# Low_Pass_Filter.net
KiCad netlist of a schematic drawn in Altium Designer
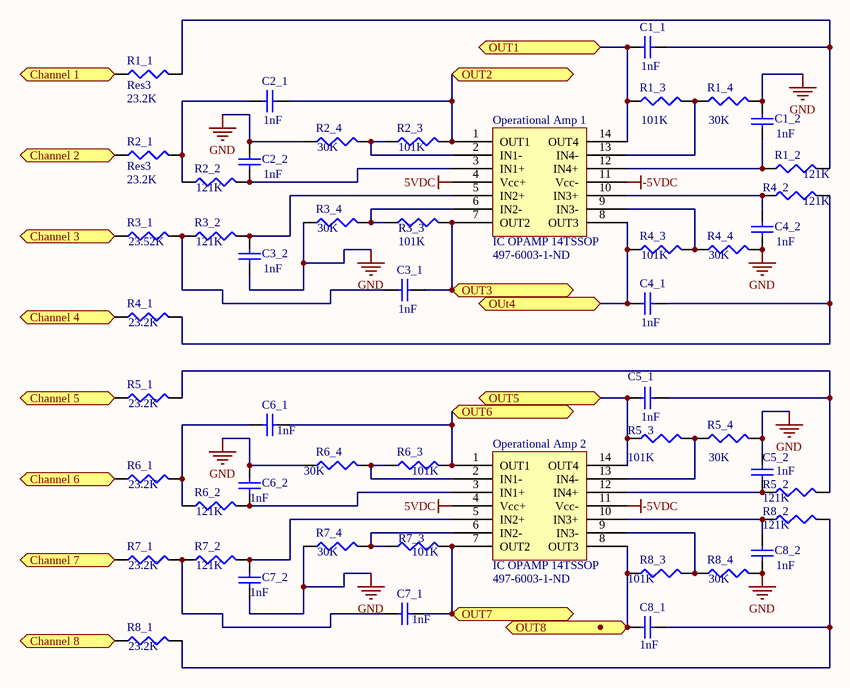
[diagram p0: Low Pass Filter.SchDoc]

(export (version "E")
  (design (tool "Eeschema 10.0.6"))
  (components
    (comp (ref "C1_1")
      (value "1nF")
      (footprint "6-0805_N")
      (description "Capacitor (Semiconductor SIM Model)")
      (fields (field (name "Comment") "Cap Semi") (field (name "PUBLISHER") "Altium Limited"))
      (libsource (lib "Miscellaneous Devices") (part "Cap Semi"))
    )
    (comp (ref "C1_2")
      (value "1nF")
      (footprint "6-0805_N")
      (description "Capacitor (Semiconductor SIM Model)")
      (fields (field (name "Comment") "Cap Semi") (field (name "PUBLISHER") "Altium Limited"))
      (libsource (lib "Miscellaneous Devices") (part "Cap Semi"))
    )
    (comp (ref "C2_1")
      (value "1nF")
      (footprint "6-0805_N")
      (description "Capacitor (Semiconductor SIM Model)")
      (fields (field (name "Comment") "Cap Semi") (field (name "PUBLISHER") "Altium Limited"))
      (libsource (lib "Miscellaneous Devices") (part "Cap Semi"))
    )
    (comp (ref "C2_2")
      (value "1nF")
      (footprint "6-0805_N")
      (description "Capacitor (Semiconductor SIM Model)")
      (fields (field (name "Comment") "Cap Semi") (field (name "PUBLISHER") "Altium Limited"))
      (libsource (lib "Miscellaneous Devices") (part "Cap Semi"))
    )
    (comp (ref "C3_1")
      (value "1nF")
      (footprint "6-0805_N")
      (description "Capacitor (Semiconductor SIM Model)")
      (fields (field (name "Comment") "Cap Semi") (field (name "PUBLISHER") "Altium Limited"))
      (libsource (lib "Miscellaneous Devices") (part "Cap Semi"))
    )
    (comp (ref "C3_2")
      (value "1nF")
      (footprint "6-0805_N")
      (description "Capacitor (Semiconductor SIM Model)")
      (fields (field (name "Comment") "Cap Semi") (field (name "PUBLISHER") "Altium Limited"))
      (libsource (lib "Miscellaneous Devices") (part "Cap Semi"))
    )
    (comp (ref "C4_1")
      (value "1nF")
      (footprint "6-0805_N")
      (description "Capacitor (Semiconductor SIM Model)")
      (fields (field (name "Comment") "Cap Semi") (field (name "PUBLISHER") "Altium Limited"))
      (libsource (lib "Miscellaneous Devices") (part "Cap Semi"))
    )
    (comp (ref "C4_2")
      (value "1nF")
      (footprint "6-0805_N")
      (description "Capacitor (Semiconductor SIM Model)")
      (fields (field (name "Comment") "Cap Semi") (field (name "PUBLISHER") "Altium Limited"))
      (libsource (lib "Miscellaneous Devices") (part "Cap Semi"))
    )
    (comp (ref "C5_1")
      (value "1nF")
      (footprint "6-0805_N")
      (description "Capacitor (Semiconductor SIM Model)")
      (fields (field (name "Comment") "Cap Semi") (field (name "PUBLISHER") "Altium Limited"))
      (libsource (lib "Miscellaneous Devices") (part "Cap Semi"))
    )
    (comp (ref "C5_2")
      (value "1nF")
      (footprint "6-0805_N")
      (description "Capacitor (Semiconductor SIM Model)")
      (fields (field (name "Comment") "Cap Semi") (field (name "PUBLISHER") "Altium Limited"))
      (libsource (lib "Miscellaneous Devices") (part "Cap Semi"))
    )
    (comp (ref "C6_1")
      (value "1nF")
      (footprint "6-0805_N")
      (description "Capacitor (Semiconductor SIM Model)")
      (fields (field (name "Comment") "Cap Semi") (field (name "PUBLISHER") "Altium Limited"))
      (libsource (lib "Miscellaneous Devices") (part "Cap Semi"))
    )
    (comp (ref "C6_2")
      (value "1nF")
      (footprint "6-0805_N")
      (description "Capacitor (Semiconductor SIM Model)")
      (fields (field (name "Comment") "Cap Semi") (field (name "PUBLISHER") "Altium Limited"))
      (libsource (lib "Miscellaneous Devices") (part "Cap Semi"))
    )
    (comp (ref "C7_1")
      (value "1nF")
      (footprint "6-0805_N")
      (description "Capacitor (Semiconductor SIM Model)")
      (fields (field (name "Comment") "Cap Semi") (field (name "PUBLISHER") "Altium Limited"))
      (libsource (lib "Miscellaneous Devices") (part "Cap Semi"))
    )
    (comp (ref "C7_2")
      (value "1nF")
      (footprint "6-0805_N")
      (description "Capacitor (Semiconductor SIM Model)")
      (fields (field (name "Comment") "Cap Semi") (field (name "PUBLISHER") "Altium Limited"))
      (libsource (lib "Miscellaneous Devices") (part "Cap Semi"))
    )
    (comp (ref "C8_1")
      (value "1nF")
      (footprint "6-0805_N")
      (description "Capacitor (Semiconductor SIM Model)")
      (fields (field (name "Comment") "Cap Semi") (field (name "PUBLISHER") "Altium Limited"))
      (libsource (lib "Miscellaneous Devices") (part "Cap Semi"))
    )
    (comp (ref "C8_2")
      (value "1nF")
      (footprint "6-0805_N")
      (description "Capacitor (Semiconductor SIM Model)")
      (fields (field (name "Comment") "Cap Semi") (field (name "PUBLISHER") "Altium Limited"))
      (libsource (lib "Miscellaneous Devices") (part "Cap Semi"))
    )
    (comp (ref "Operational Amp 1")
      (value "IC OPAMP 14TSSOP")
      (footprint "TSV994IPT")
      (fields (field (name "SUPPLIER PART NUMBER 1") "497-6003-1-ND"))
      (libsource (lib "TSV994IPT") (part "Component_1"))
    )
    (comp (ref "Operational Amp 2")
      (value "IC OPAMP 14TSSOP")
      (footprint "TSV994IPT")
      (fields (field (name "SUPPLIER PART NUMBER 1") "497-6003-1-ND"))
      (libsource (lib "TSV994IPT") (part "Component_1"))
    )
    (comp (ref "R1_1")
      (value "Res3")
      (footprint "6-0805_N")
      (description "Resistor")
      (fields (field (name "ALTIUM_VALUE") "23.2K") (field (name "PUBLISHER") "Altium Limited"))
      (libsource (lib "Miscellaneous Devices") (part "Res3"))
    )
    (comp (ref "R1_2")
      (value "121K")
      (footprint "6-0805_N")
      (description "Resistor")
      (fields (field (name "Comment") "Res3") (field (name "PUBLISHER") "Altium Limited"))
      (libsource (lib "Miscellaneous Devices") (part "Res3"))
    )
    (comp (ref "R1_3")
      (value "101K")
      (footprint "6-0805_N")
      (description "Resistor")
      (fields (field (name "Comment") "Res3") (field (name "PUBLISHER") "Altium Limited"))
      (libsource (lib "Miscellaneous Devices") (part "Res3"))
    )
    (comp (ref "R1_4")
      (value "30K")
      (footprint "6-0805_N")
      (description "Resistor")
      (fields (field (name "Comment") "Res3") (field (name "PUBLISHER") "Altium Limited"))
      (libsource (lib "Miscellaneous Devices") (part "Res3"))
    )
    (comp (ref "R2_1")
      (value "Res3")
      (footprint "6-0805_N")
      (description "Resistor")
      (fields (field (name "ALTIUM_VALUE") "23.2K") (field (name "PUBLISHER") "Altium Limited"))
      (libsource (lib "Miscellaneous Devices") (part "Res3"))
    )
    (comp (ref "R2_2")
      (value "121K")
      (footprint "6-0805_N")
      (description "Resistor")
      (fields (field (name "Comment") "Res3") (field (name "PUBLISHER") "Altium Limited"))
      (libsource (lib "Miscellaneous Devices") (part "Res3"))
    )
    (comp (ref "R2_3")
      (value "101K")
      (footprint "6-0805_N")
      (description "Resistor")
      (fields (field (name "Comment") "Res3") (field (name "PUBLISHER") "Altium Limited"))
      (libsource (lib "Miscellaneous Devices") (part "Res3"))
    )
    (comp (ref "R2_4")
      (value "30K")
      (footprint "6-0805_N")
      (description "Resistor")
      (fields (field (name "Comment") "Res3") (field (name "PUBLISHER") "Altium Limited"))
      (libsource (lib "Miscellaneous Devices") (part "Res3"))
    )
    (comp (ref "R3_1")
      (value "23.52K")
      (footprint "6-0805_N")
      (description "Resistor")
      (fields (field (name "Comment") "Res3") (field (name "PUBLISHER") "Altium Limited"))
      (libsource (lib "Miscellaneous Devices") (part "Res3"))
    )
    (comp (ref "R3_2")
      (value "121K")
      (footprint "6-0805_N")
      (description "Resistor")
      (fields (field (name "Comment") "Res3") (field (name "PUBLISHER") "Altium Limited"))
      (libsource (lib "Miscellaneous Devices") (part "Res3"))
    )
    (comp (ref "R3_3")
      (value "101K")
      (footprint "6-0805_N")
      (description "Resistor")
      (fields (field (name "Comment") "Res3") (field (name "PUBLISHER") "Altium Limited"))
      (libsource (lib "Miscellaneous Devices") (part "Res3"))
    )
    (comp (ref "R3_4")
      (value "30K")
      (footprint "6-0805_N")
      (description "Resistor")
      (fields (field (name "Comment") "Res3") (field (name "PUBLISHER") "Altium Limited"))
      (libsource (lib "Miscellaneous Devices") (part "Res3"))
    )
    (comp (ref "R4_1")
      (value "23.2K")
      (footprint "6-0805_N")
      (description "Resistor")
      (fields (field (name "Comment") "Res3") (field (name "PUBLISHER") "Altium Limited"))
      (libsource (lib "Miscellaneous Devices") (part "Res3"))
    )
    (comp (ref "R4_2")
      (value "121K")
      (footprint "6-0805_N")
      (description "Resistor")
      (fields (field (name "Comment") "Res3") (field (name "PUBLISHER") "Altium Limited"))
      (libsource (lib "Miscellaneous Devices") (part "Res3"))
    )
    (comp (ref "R4_3")
      (value "101K")
      (footprint "6-0805_N")
      (description "Resistor")
      (fields (field (name "Comment") "Res3") (field (name "PUBLISHER") "Altium Limited"))
      (libsource (lib "Miscellaneous Devices") (part "Res3"))
    )
    (comp (ref "R4_4")
      (value "30K")
      (footprint "6-0805_N")
      (description "Resistor")
      (fields (field (name "Comment") "Res3") (field (name "PUBLISHER") "Altium Limited"))
      (libsource (lib "Miscellaneous Devices") (part "Res3"))
    )
    (comp (ref "R5_1")
      (value "23.2K")
      (footprint "6-0805_N")
      (description "Resistor")
      (fields (field (name "Comment") "Res3") (field (name "PUBLISHER") "Altium Limited"))
      (libsource (lib "Miscellaneous Devices") (part "Res3"))
    )
    (comp (ref "R5_2")
      (value "121K")
      (footprint "6-0805_N")
      (description "Resistor")
      (fields (field (name "Comment") "Res3") (field (name "PUBLISHER") "Altium Limited"))
      (libsource (lib "Miscellaneous Devices") (part "Res3"))
    )
    (comp (ref "R5_3")
      (value "101K")
      (footprint "6-0805_N")
      (description "Resistor")
      (fields (field (name "Comment") "Res3") (field (name "PUBLISHER") "Altium Limited"))
      (libsource (lib "Miscellaneous Devices") (part "Res3"))
    )
    (comp (ref "R5_4")
      (value "30K")
      (footprint "6-0805_N")
      (description "Resistor")
      (fields (field (name "Comment") "Res3") (field (name "PUBLISHER") "Altium Limited"))
      (libsource (lib "Miscellaneous Devices") (part "Res3"))
    )
    (comp (ref "R6_1")
      (value "23.2K")
      (footprint "6-0805_N")
      (description "Resistor")
      (fields (field (name "Comment") "Res3") (field (name "PUBLISHER") "Altium Limited"))
      (libsource (lib "Miscellaneous Devices") (part "Res3"))
    )
    (comp (ref "R6_2")
      (value "121K")
      (footprint "6-0805_N")
      (description "Resistor")
      (fields (field (name "Comment") "Res3") (field (name "PUBLISHER") "Altium Limited"))
      (libsource (lib "Miscellaneous Devices") (part "Res3"))
    )
    (comp (ref "R6_3")
      (value "101K")
      (footprint "6-0805_N")
      (description "Resistor")
      (fields (field (name "Comment") "Res3") (field (name "PUBLISHER") "Altium Limited"))
      (libsource (lib "Miscellaneous Devices") (part "Res3"))
    )
    (comp (ref "R6_4")
      (value "30K")
      (footprint "6-0805_N")
      (description "Resistor")
      (fields (field (name "Comment") "Res3") (field (name "PUBLISHER") "Altium Limited"))
      (libsource (lib "Miscellaneous Devices") (part "Res3"))
    )
    (comp (ref "R7_1")
      (value "23.2K")
      (footprint "6-0805_N")
      (description "Resistor")
      (fields (field (name "Comment") "Res3") (field (name "PUBLISHER") "Altium Limited"))
      (libsource (lib "Miscellaneous Devices") (part "Res3"))
    )
    (comp (ref "R7_2")
      (value "121K")
      (footprint "6-0805_N")
      (description "Resistor")
      (fields (field (name "Comment") "Res3") (field (name "PUBLISHER") "Altium Limited"))
      (libsource (lib "Miscellaneous Devices") (part "Res3"))
    )
    (comp (ref "R7_3")
      (value "101K")
      (footprint "6-0805_N")
      (description "Resistor")
      (fields (field (name "Comment") "Res3") (field (name "PUBLISHER") "Altium Limited"))
      (libsource (lib "Miscellaneous Devices") (part "Res3"))
    )
    (comp (ref "R7_4")
      (value "30K")
      (footprint "6-0805_N")
      (description "Resistor")
      (fields (field (name "Comment") "Res3") (field (name "PUBLISHER") "Altium Limited"))
      (libsource (lib "Miscellaneous Devices") (part "Res3"))
    )
    (comp (ref "R8_1")
      (value "23.2K")
      (footprint "6-0805_N")
      (description "Resistor")
      (fields (field (name "Comment") "Res3") (field (name "PUBLISHER") "Altium Limited"))
      (libsource (lib "Miscellaneous Devices") (part "Res3"))
    )
    (comp (ref "R8_2")
      (value "121K")
      (footprint "6-0805_N")
      (description "Resistor")
      (fields (field (name "Comment") "Res3") (field (name "PUBLISHER") "Altium Limited"))
      (libsource (lib "Miscellaneous Devices") (part "Res3"))
    )
    (comp (ref "R8_3")
      (value "101K")
      (footprint "6-0805_N")
      (description "Resistor")
      (fields (field (name "Comment") "Res3") (field (name "PUBLISHER") "Altium Limited"))
      (libsource (lib "Miscellaneous Devices") (part "Res3"))
    )
    (comp (ref "R8_4")
      (value "30K")
      (footprint "6-0805_N")
      (description "Resistor")
      (fields (field (name "Comment") "Res3") (field (name "PUBLISHER") "Altium Limited"))
      (libsource (lib "Miscellaneous Devices") (part "Res3"))
    )
  )
  (nets
    (net (code "1") (name "-5VDC") (class "Default")
      (node (ref "Operational Amp 1") (pin "11") (pinfunction "Vcc-_11") (pintype "passive"))
      (node (ref "Operational Amp 2") (pin "11") (pinfunction "Vcc-_11") (pintype "passive"))
    )
    (net (code "2") (name "/Channel 1") (class "Default")
      (node (ref "R1_1") (pin "1") (pinfunction "1_1") (pintype "passive"))
    )
    (net (code "3") (name "/Channel 2") (class "Default")
      (node (ref "R2_1") (pin "1") (pinfunction "1_1") (pintype "passive"))
    )
    (net (code "4") (name "/Channel 3") (class "Default")
      (node (ref "R3_1") (pin "1") (pinfunction "1_1") (pintype "passive"))
    )
    (net (code "5") (name "/Channel 4") (class "Default")
      (node (ref "R4_1") (pin "1") (pinfunction "1_1") (pintype "passive"))
    )
    (net (code "6") (name "/Channel 5") (class "Default")
      (node (ref "R5_1") (pin "1") (pinfunction "1_1") (pintype "passive"))
    )
    (net (code "7") (name "/Channel 6") (class "Default")
      (node (ref "R6_1") (pin "1") (pinfunction "1_1") (pintype "passive"))
    )
    (net (code "8") (name "/Channel 7") (class "Default")
      (node (ref "R7_1") (pin "1") (pinfunction "1_1") (pintype "passive"))
    )
    (net (code "9") (name "/Channel 8") (class "Default")
      (node (ref "R8_1") (pin "1") (pinfunction "1_1") (pintype "passive"))
    )
    (net (code "10") (name "/OUT1") (class "Default")
      (node (ref "C1_1") (pin "1") (pinfunction "1_1") (pintype "passive"))
      (node (ref "Operational Amp 1") (pin "14") (pinfunction "OUT4_14") (pintype "passive"))
      (node (ref "R1_3") (pin "1") (pinfunction "1_1") (pintype "passive"))
    )
    (net (code "11") (name "/OUT2") (class "Default")
      (node (ref "C2_1") (pin "2") (pinfunction "2_2") (pintype "passive"))
      (node (ref "Operational Amp 1") (pin "1") (pinfunction "OUT1_1") (pintype "passive"))
      (node (ref "R2_3") (pin "2") (pinfunction "2_2") (pintype "passive"))
    )
    (net (code "12") (name "/OUT3") (class "Default")
      (node (ref "C3_1") (pin "2") (pinfunction "2_2") (pintype "passive"))
      (node (ref "Operational Amp 1") (pin "7") (pinfunction "OUT2_7") (pintype "passive"))
      (node (ref "R3_3") (pin "2") (pinfunction "2_2") (pintype "passive"))
    )
    (net (code "13") (name "/OUT5") (class "Default")
      (node (ref "C5_1") (pin "1") (pinfunction "1_1") (pintype "passive"))
      (node (ref "Operational Amp 2") (pin "14") (pinfunction "OUT4_14") (pintype "passive"))
      (node (ref "R5_3") (pin "1") (pinfunction "1_1") (pintype "passive"))
    )
    (net (code "14") (name "/OUT6") (class "Default")
      (node (ref "C6_1") (pin "2") (pinfunction "2_2") (pintype "passive"))
      (node (ref "Operational Amp 2") (pin "1") (pinfunction "OUT1_1") (pintype "passive"))
      (node (ref "R6_3") (pin "2") (pinfunction "2_2") (pintype "passive"))
    )
    (net (code "15") (name "/OUT7") (class "Default")
      (node (ref "C7_1") (pin "2") (pinfunction "2_2") (pintype "passive"))
      (node (ref "Operational Amp 2") (pin "7") (pinfunction "OUT2_7") (pintype "passive"))
      (node (ref "R7_3") (pin "2") (pinfunction "2_2") (pintype "passive"))
    )
    (net (code "16") (name "/OUT8") (class "Default")
      (node (ref "C8_1") (pin "2") (pinfunction "2_2") (pintype "passive"))
      (node (ref "Operational Amp 2") (pin "8") (pinfunction "OUT3_8") (pintype "passive"))
      (node (ref "R8_3") (pin "1") (pinfunction "1_1") (pintype "passive"))
    )
    (net (code "17") (name "/OUt4") (class "Default")
      (node (ref "C4_1") (pin "1") (pinfunction "1_1") (pintype "passive"))
      (node (ref "Operational Amp 1") (pin "8") (pinfunction "OUT3_8") (pintype "passive"))
      (node (ref "R4_3") (pin "1") (pinfunction "1_1") (pintype "passive"))
    )
    (net (code "18") (name "5VDC") (class "Default")
      (node (ref "Operational Amp 1") (pin "4") (pinfunction "Vcc+_4") (pintype "passive"))
      (node (ref "Operational Amp 2") (pin "4") (pinfunction "Vcc+_4") (pintype "passive"))
    )
    (net (code "19") (name "GND") (class "Default")
      (node (ref "C1_2") (pin "1") (pinfunction "1_1") (pintype "passive"))
      (node (ref "C2_2") (pin "2") (pinfunction "2_2") (pintype "passive"))
      (node (ref "C3_2") (pin "1") (pinfunction "1_1") (pintype "passive"))
      (node (ref "C4_2") (pin "1") (pinfunction "1_1") (pintype "passive"))
      (node (ref "C5_2") (pin "2") (pinfunction "2_2") (pintype "passive"))
      (node (ref "C6_2") (pin "2") (pinfunction "2_2") (pintype "passive"))
      (node (ref "C7_2") (pin "1") (pinfunction "1_1") (pintype "passive"))
      (node (ref "C8_2") (pin "1") (pinfunction "1_1") (pintype "passive"))
      (node (ref "R1_4") (pin "2") (pinfunction "2_2") (pintype "passive"))
      (node (ref "R2_4") (pin "1") (pinfunction "1_1") (pintype "passive"))
      (node (ref "R3_4") (pin "1") (pinfunction "1_1") (pintype "passive"))
      (node (ref "R4_4") (pin "2") (pinfunction "2_2") (pintype "passive"))
      (node (ref "R5_4") (pin "2") (pinfunction "2_2") (pintype "passive"))
      (node (ref "R6_4") (pin "1") (pinfunction "1_1") (pintype "passive"))
      (node (ref "R7_4") (pin "1") (pinfunction "1_1") (pintype "passive"))
      (node (ref "R8_4") (pin "2") (pinfunction "2_2") (pintype "passive"))
    )
    (net (code "20") (name "Net-(C1_1-Pad2)") (class "Default")
      (node (ref "C1_1") (pin "2") (pinfunction "2_2") (pintype "passive"))
      (node (ref "R1_1") (pin "2") (pinfunction "2_2") (pintype "passive"))
      (node (ref "R1_2") (pin "2") (pinfunction "2_2") (pintype "passive"))
    )
    (net (code "21") (name "Net-(C2_1-Pad1)") (class "Default")
      (node (ref "C2_1") (pin "1") (pinfunction "1_1") (pintype "passive"))
      (node (ref "R2_1") (pin "2") (pinfunction "2_2") (pintype "passive"))
      (node (ref "R2_2") (pin "1") (pinfunction "1_1") (pintype "passive"))
    )
    (net (code "22") (name "Net-(C3_1-Pad1)") (class "Default")
      (node (ref "C3_1") (pin "1") (pinfunction "1_1") (pintype "passive"))
      (node (ref "R3_1") (pin "2") (pinfunction "2_2") (pintype "passive"))
      (node (ref "R3_2") (pin "1") (pinfunction "1_1") (pintype "passive"))
    )
    (net (code "23") (name "Net-(C4_1-Pad2)") (class "Default")
      (node (ref "C4_1") (pin "2") (pinfunction "2_2") (pintype "passive"))
      (node (ref "R4_1") (pin "2") (pinfunction "2_2") (pintype "passive"))
      (node (ref "R4_2") (pin "2") (pinfunction "2_2") (pintype "passive"))
    )
    (net (code "24") (name "Net-(C5_1-Pad2)") (class "Default")
      (node (ref "C5_1") (pin "2") (pinfunction "2_2") (pintype "passive"))
      (node (ref "R5_1") (pin "2") (pinfunction "2_2") (pintype "passive"))
      (node (ref "R5_2") (pin "2") (pinfunction "2_2") (pintype "passive"))
    )
    (net (code "25") (name "Net-(C6_1-Pad1)") (class "Default")
      (node (ref "C6_1") (pin "1") (pinfunction "1_1") (pintype "passive"))
      (node (ref "R6_1") (pin "2") (pinfunction "2_2") (pintype "passive"))
      (node (ref "R6_2") (pin "1") (pinfunction "1_1") (pintype "passive"))
    )
    (net (code "26") (name "Net-(C7_1-Pad1)") (class "Default")
      (node (ref "C7_1") (pin "1") (pinfunction "1_1") (pintype "passive"))
      (node (ref "R7_1") (pin "2") (pinfunction "2_2") (pintype "passive"))
      (node (ref "R7_2") (pin "1") (pinfunction "1_1") (pintype "passive"))
    )
    (net (code "27") (name "Net-(C8_1-Pad1)") (class "Default")
      (node (ref "C8_1") (pin "1") (pinfunction "1_1") (pintype "passive"))
      (node (ref "R8_1") (pin "2") (pinfunction "2_2") (pintype "passive"))
      (node (ref "R8_2") (pin "2") (pinfunction "2_2") (pintype "passive"))
    )
    (net (code "28") (name "Net-(Operational Amp 1-IN1+)") (class "Default")
      (node (ref "C2_2") (pin "1") (pinfunction "1_1") (pintype "passive"))
      (node (ref "Operational Amp 1") (pin "3") (pinfunction "IN1+_3") (pintype "passive"))
      (node (ref "R2_2") (pin "2") (pinfunction "2_2") (pintype "passive"))
    )
    (net (code "29") (name "Net-(Operational Amp 1-IN1-)") (class "Default")
      (node (ref "Operational Amp 1") (pin "2") (pinfunction "IN1-_2") (pintype "passive"))
      (node (ref "R2_3") (pin "1") (pinfunction "1_1") (pintype "passive"))
      (node (ref "R2_4") (pin "2") (pinfunction "2_2") (pintype "passive"))
    )
    (net (code "30") (name "Net-(Operational Amp 1-IN2+)") (class "Default")
      (node (ref "C3_2") (pin "2") (pinfunction "2_2") (pintype "passive"))
      (node (ref "Operational Amp 1") (pin "5") (pinfunction "IN2+_5") (pintype "passive"))
      (node (ref "R3_2") (pin "2") (pinfunction "2_2") (pintype "passive"))
    )
    (net (code "31") (name "Net-(Operational Amp 1-IN2-)") (class "Default")
      (node (ref "Operational Amp 1") (pin "6") (pinfunction "IN2-_6") (pintype "passive"))
      (node (ref "R3_3") (pin "1") (pinfunction "1_1") (pintype "passive"))
      (node (ref "R3_4") (pin "2") (pinfunction "2_2") (pintype "passive"))
    )
    (net (code "32") (name "Net-(Operational Amp 1-IN3+)") (class "Default")
      (node (ref "C4_2") (pin "2") (pinfunction "2_2") (pintype "passive"))
      (node (ref "Operational Amp 1") (pin "10") (pinfunction "IN3+_10") (pintype "passive"))
      (node (ref "R4_2") (pin "1") (pinfunction "1_1") (pintype "passive"))
    )
    (net (code "33") (name "Net-(Operational Amp 1-IN3-)") (class "Default")
      (node (ref "Operational Amp 1") (pin "9") (pinfunction "IN3-_9") (pintype "passive"))
      (node (ref "R4_3") (pin "2") (pinfunction "2_2") (pintype "passive"))
      (node (ref "R4_4") (pin "1") (pinfunction "1_1") (pintype "passive"))
    )
    (net (code "34") (name "Net-(Operational Amp 1-IN4+)") (class "Default")
      (node (ref "C1_2") (pin "2") (pinfunction "2_2") (pintype "passive"))
      (node (ref "Operational Amp 1") (pin "12") (pinfunction "IN4+_12") (pintype "passive"))
      (node (ref "R1_2") (pin "1") (pinfunction "1_1") (pintype "passive"))
    )
    (net (code "35") (name "Net-(Operational Amp 1-IN4-)") (class "Default")
      (node (ref "Operational Amp 1") (pin "13") (pinfunction "IN4-_13") (pintype "passive"))
      (node (ref "R1_3") (pin "2") (pinfunction "2_2") (pintype "passive"))
      (node (ref "R1_4") (pin "1") (pinfunction "1_1") (pintype "passive"))
    )
    (net (code "36") (name "Net-(Operational Amp 2-IN1+)") (class "Default")
      (node (ref "C6_2") (pin "1") (pinfunction "1_1") (pintype "passive"))
      (node (ref "Operational Amp 2") (pin "3") (pinfunction "IN1+_3") (pintype "passive"))
      (node (ref "R6_2") (pin "2") (pinfunction "2_2") (pintype "passive"))
    )
    (net (code "37") (name "Net-(Operational Amp 2-IN1-)") (class "Default")
      (node (ref "Operational Amp 2") (pin "2") (pinfunction "IN1-_2") (pintype "passive"))
      (node (ref "R6_3") (pin "1") (pinfunction "1_1") (pintype "passive"))
      (node (ref "R6_4") (pin "2") (pinfunction "2_2") (pintype "passive"))
    )
    (net (code "38") (name "Net-(Operational Amp 2-IN2+)") (class "Default")
      (node (ref "C7_2") (pin "2") (pinfunction "2_2") (pintype "passive"))
      (node (ref "Operational Amp 2") (pin "5") (pinfunction "IN2+_5") (pintype "passive"))
      (node (ref "R7_2") (pin "2") (pinfunction "2_2") (pintype "passive"))
    )
    (net (code "39") (name "Net-(Operational Amp 2-IN2-)") (class "Default")
      (node (ref "Operational Amp 2") (pin "6") (pinfunction "IN2-_6") (pintype "passive"))
      (node (ref "R7_3") (pin "1") (pinfunction "1_1") (pintype "passive"))
      (node (ref "R7_4") (pin "2") (pinfunction "2_2") (pintype "passive"))
    )
    (net (code "40") (name "Net-(Operational Amp 2-IN3+)") (class "Default")
      (node (ref "C8_2") (pin "2") (pinfunction "2_2") (pintype "passive"))
      (node (ref "Operational Amp 2") (pin "10") (pinfunction "IN3+_10") (pintype "passive"))
      (node (ref "R8_2") (pin "1") (pinfunction "1_1") (pintype "passive"))
    )
    (net (code "41") (name "Net-(Operational Amp 2-IN3-)") (class "Default")
      (node (ref "Operational Amp 2") (pin "9") (pinfunction "IN3-_9") (pintype "passive"))
      (node (ref "R8_3") (pin "2") (pinfunction "2_2") (pintype "passive"))
      (node (ref "R8_4") (pin "1") (pinfunction "1_1") (pintype "passive"))
    )
    (net (code "42") (name "Net-(Operational Amp 2-IN4+)") (class "Default")
      (node (ref "C5_2") (pin "1") (pinfunction "1_1") (pintype "passive"))
      (node (ref "Operational Amp 2") (pin "12") (pinfunction "IN4+_12") (pintype "passive"))
      (node (ref "R5_2") (pin "1") (pinfunction "1_1") (pintype "passive"))
    )
    (net (code "43") (name "Net-(Operational Amp 2-IN4-)") (class "Default")
      (node (ref "Operational Amp 2") (pin "13") (pinfunction "IN4-_13") (pintype "passive"))
      (node (ref "R5_3") (pin "2") (pinfunction "2_2") (pintype "passive"))
      (node (ref "R5_4") (pin "1") (pinfunction "1_1") (pintype "passive"))
    )
  )
)
